# Motor_Circuit.net
KiCad netlist of a schematic drawn in Altium Designer
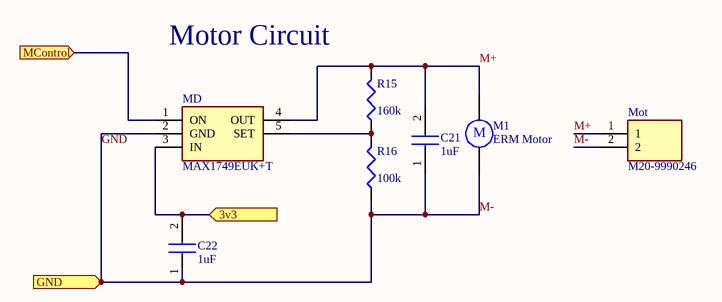
[diagram p0: Motor Circuit.SchDoc]

(export (version "E")
  (design (tool "Eeschema 10.0.6"))
  (components
    (comp (ref "C21")
      (value "1uF")
      (footprint "SamacSys:CAPC1608X90N")
      (description "Capacitor, 0603YC10JAT2A")
      (fields
        (field (name "MANUFACTURER_PART_NUMBER") "0603YC105JAT2A")
        (field (name "MOUSER PART NUMBER") "581-0603YC105JAT2A")
      )
      (libsource (lib "*") (part "0603YC105JAT2A"))
    )
    (comp (ref "C22")
      (value "1uF")
      (footprint "SamacSys:CAPC1608X90N")
      (description "Capacitor, 0603YC10JAT2A")
      (fields
        (field (name "MANUFACTURER_PART_NUMBER") "0603YC105JAT2A")
        (field (name "MOUSER PART NUMBER") "581-0603YC105JAT2A")
      )
      (libsource (lib "*") (part "0603YC105JAT2A"))
    )
    (comp (ref "M1")
      (value "ERM Motor")
      (footprint "RB5-10.5")
      (description "VC1234B016F")
      (fields (field (name "PUBLISHER") "Altium Limited"))
      (libsource (lib "Miscellaneous Devices") (part "Motor"))
    )
    (comp (ref "MD")
      (value "MAX1749EUK+T")
      (footprint "SamacSys:SOT95P280X145-5N")
      (description "Integrated Circuit")
      (libsource (lib "*") (part "MAX1749EUK+T"))
    )
    (comp (ref "Mot")
      (value "M20-9990246")
      (footprint "SamacSys:HDRV2W66P0X254_1X2_508X254X874P")
      (description "Connector")
      (fields (field (name "MOUSER PART NUMBER") "855-M20-9990246"))
      (libsource (lib "*") (part "M20-9990246"))
    )
    (comp (ref "R15")
      (value "160k")
      (footprint "J1-0603")
      (description "Resistor")
      (fields (field (name "Comment") "Res3") (field (name "PUBLISHER") "Altium Limited"))
      (libsource (lib "Miscellaneous Devices") (part "Res3"))
    )
    (comp (ref "R16")
      (value "100k")
      (footprint "J1-0603")
      (description "Resistor")
      (fields (field (name "Comment") "Res3") (field (name "PUBLISHER") "Altium Limited"))
      (libsource (lib "Miscellaneous Devices") (part "Res3"))
    )
  )
  (nets
    (net (code "1") (name "/3v3") (class "Default")
      (node (ref "C22") (pin "2") (pinfunction "2_2") (pintype "passive"))
      (node (ref "MD") (pin "3") (pinfunction "IN_3") (pintype "passive"))
    )
    (net (code "2") (name "/GND") (class "Default")
      (node (ref "C21") (pin "1") (pinfunction "1_1") (pintype "passive"))
      (node (ref "C22") (pin "1") (pinfunction "1_1") (pintype "passive"))
      (node (ref "M1") (pin "2") (pinfunction "2_2") (pintype "passive"))
      (node (ref "MD") (pin "2") (pinfunction "GND_2") (pintype "passive"))
      (node (ref "Mot") (pin "2") (pinfunction "2_2") (pintype "passive"))
      (node (ref "R16") (pin "1") (pinfunction "1_1") (pintype "passive"))
    )
    (net (code "3") (name "/M+") (class "Default")
      (node (ref "C21") (pin "2") (pinfunction "2_2") (pintype "passive"))
      (node (ref "M1") (pin "1") (pinfunction "1_1") (pintype "passive"))
      (node (ref "MD") (pin "4") (pinfunction "OUT_4") (pintype "passive"))
      (node (ref "Mot") (pin "1") (pinfunction "1_1") (pintype "passive"))
      (node (ref "R15") (pin "2") (pinfunction "2_2") (pintype "passive"))
    )
    (net (code "4") (name "/MControl") (class "Default")
      (node (ref "MD") (pin "1") (pinfunction "ON_1") (pintype "passive"))
    )
    (net (code "5") (name "Net-(MD-SET)") (class "Default")
      (node (ref "MD") (pin "5") (pinfunction "SET_5") (pintype "passive"))
      (node (ref "R15") (pin "1") (pinfunction "1_1") (pintype "passive"))
      (node (ref "R16") (pin "2") (pinfunction "2_2") (pintype "passive"))
    )
  )
)
